# Motor_Mount_2024_Feb_07.net
KiCad netlist of a schematic drawn in EasyEDA
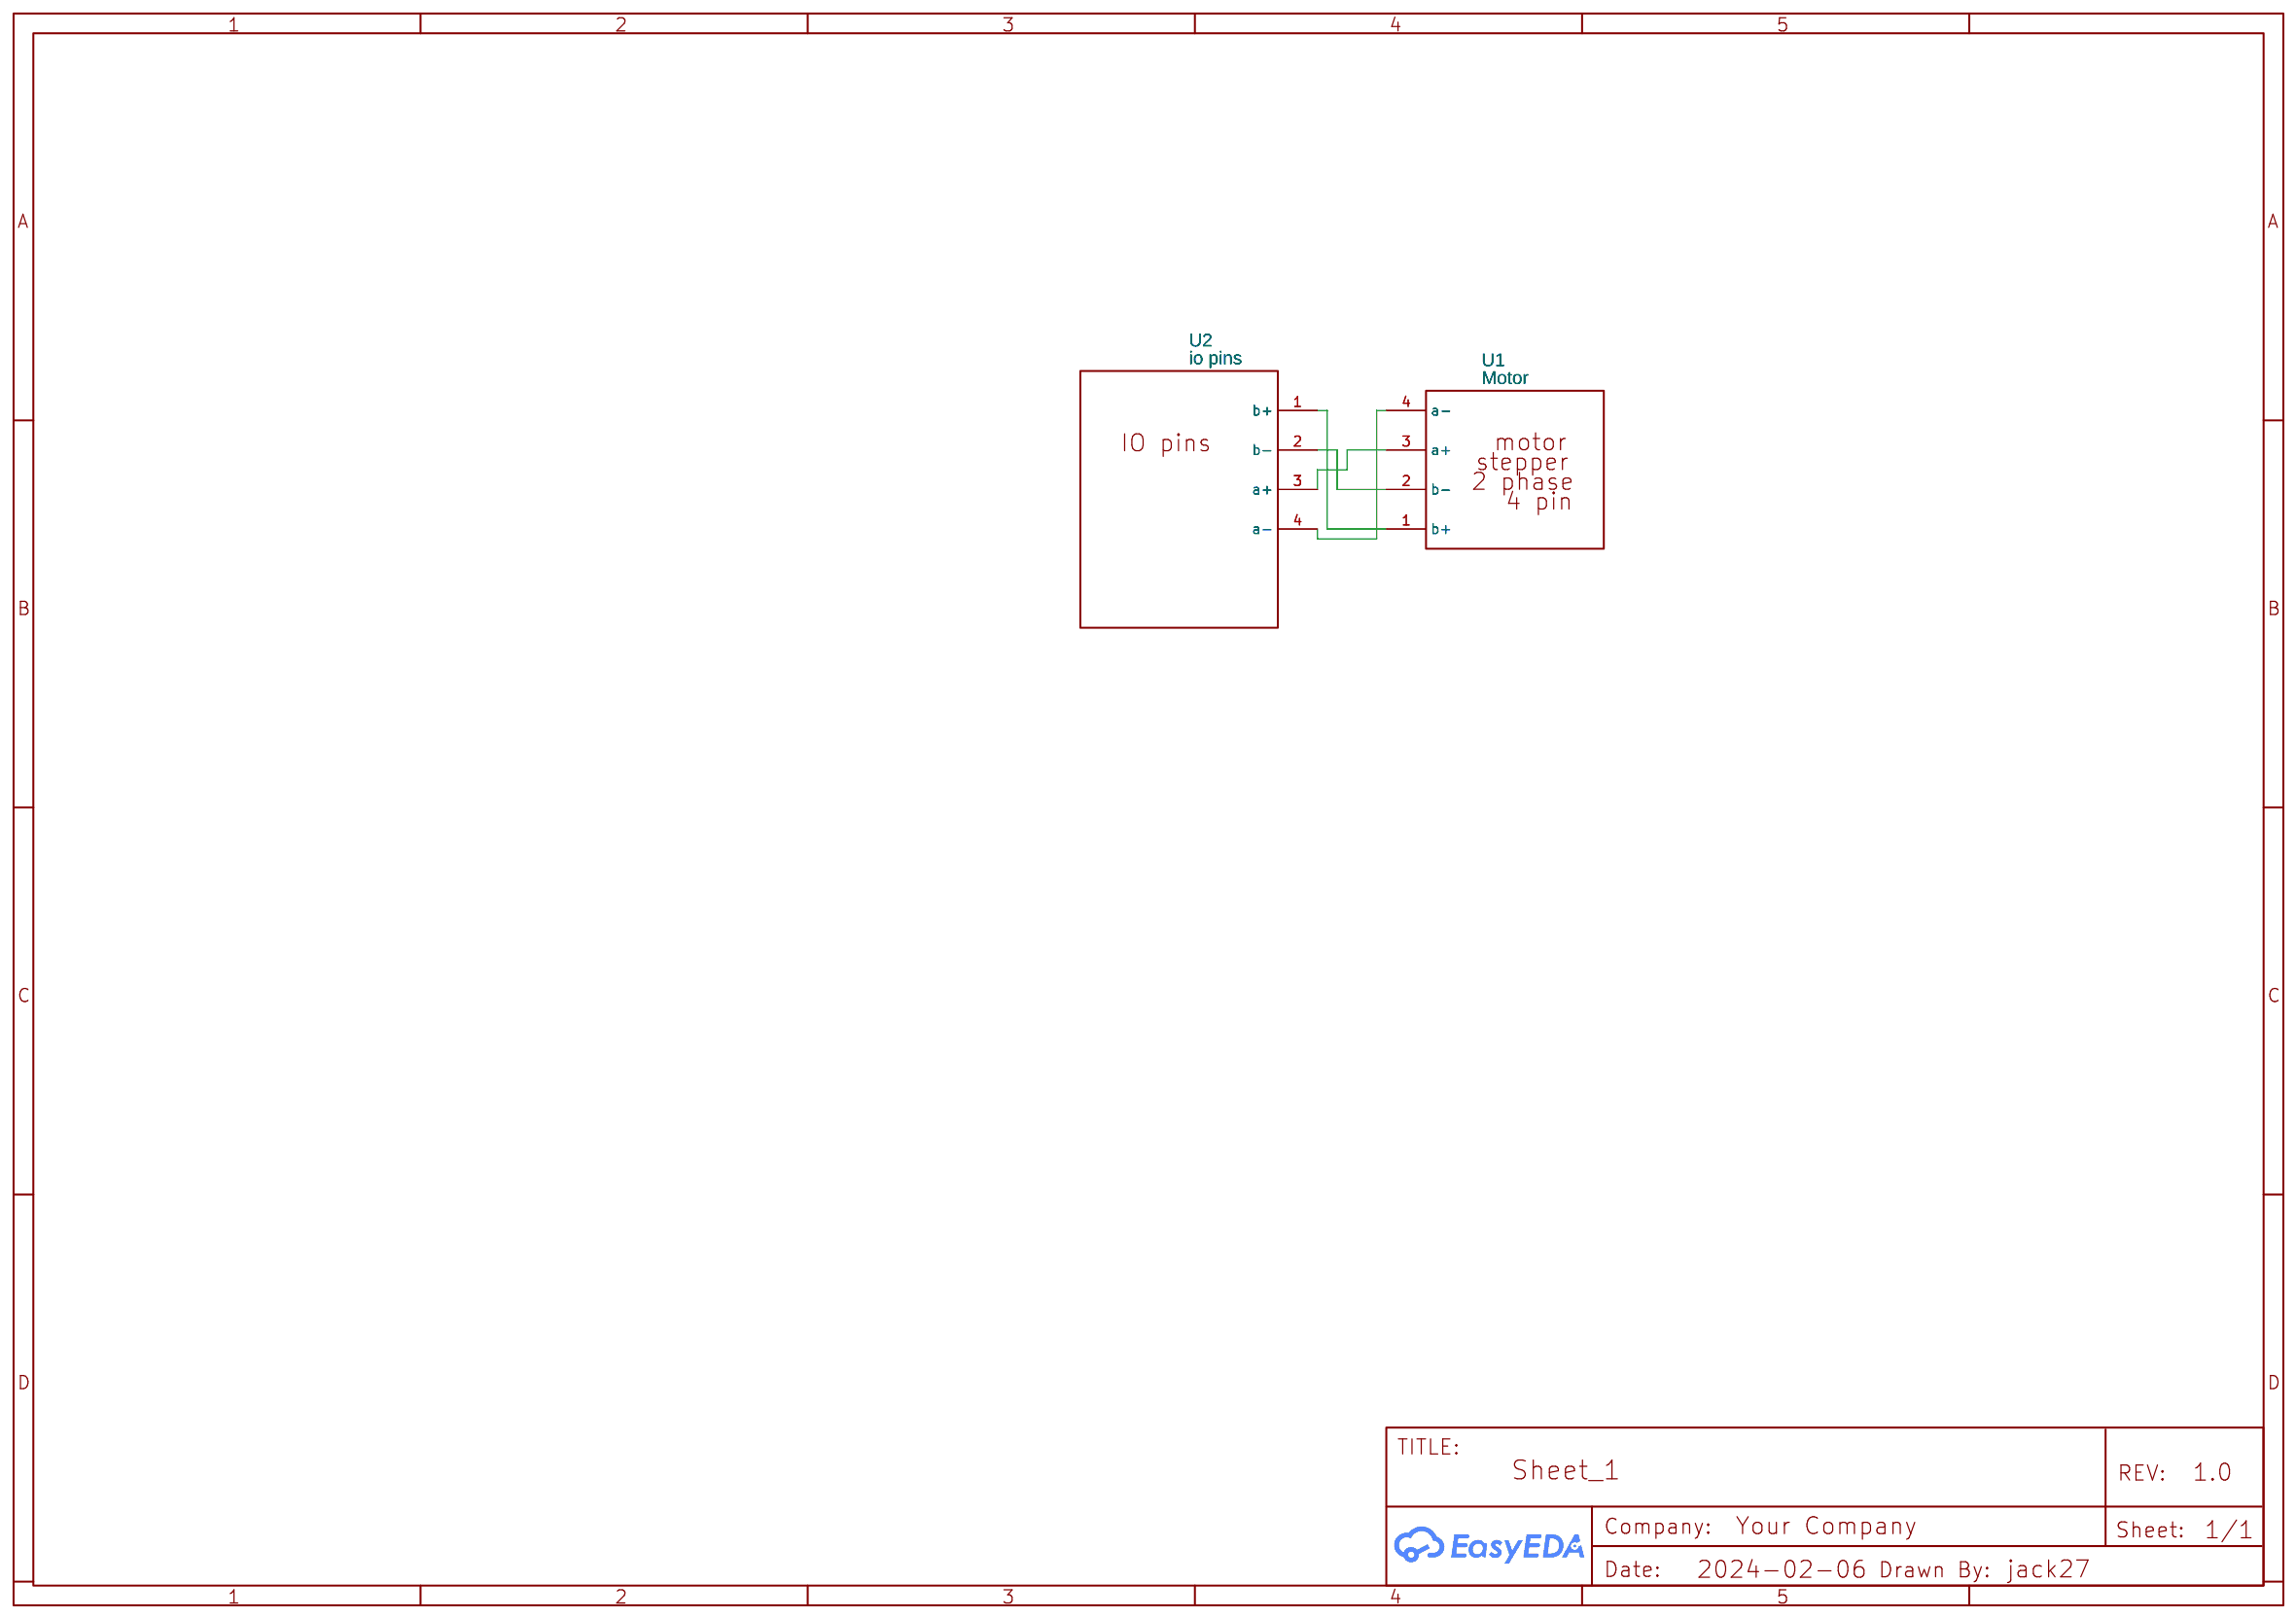
[diagram p0: schematic sheet]

(export (version "E")
  (design (tool "Eeschema 10.0.6"))
  (components
    (comp (ref "U1") (value "Motor") (libsource (lib "") (part "Motor")))
    (comp (ref "U2") (value "io pins") (libsource (lib "") (part "io pins")))
  )
  (nets
    (net (code "1") (name "Net-(U1-a+)") (class "Default")
      (node (ref "U1") (pin "3") (pinfunction "a+_3") (pintype "unspecified"))
      (node (ref "U2") (pin "3") (pinfunction "a+_3") (pintype "unspecified"))
    )
    (net (code "2") (name "Net-(U1-a-)") (class "Default")
      (node (ref "U1") (pin "4") (pinfunction "a-_4") (pintype "unspecified"))
      (node (ref "U2") (pin "4") (pinfunction "a-_4") (pintype "unspecified"))
    )
    (net (code "3") (name "Net-(U1-b+)") (class "Default")
      (node (ref "U1") (pin "1") (pinfunction "b+_1") (pintype "unspecified"))
      (node (ref "U2") (pin "1") (pinfunction "b+_1") (pintype "unspecified"))
    )
    (net (code "4") (name "Net-(U1-b-)") (class "Default")
      (node (ref "U1") (pin "2") (pinfunction "b-_2") (pintype "unspecified"))
      (node (ref "U2") (pin "2") (pinfunction "b-_2") (pintype "unspecified"))
    )
  )
)
